# ESP32_Custom.net
KiCad netlist of a schematic drawn in Altium Designer
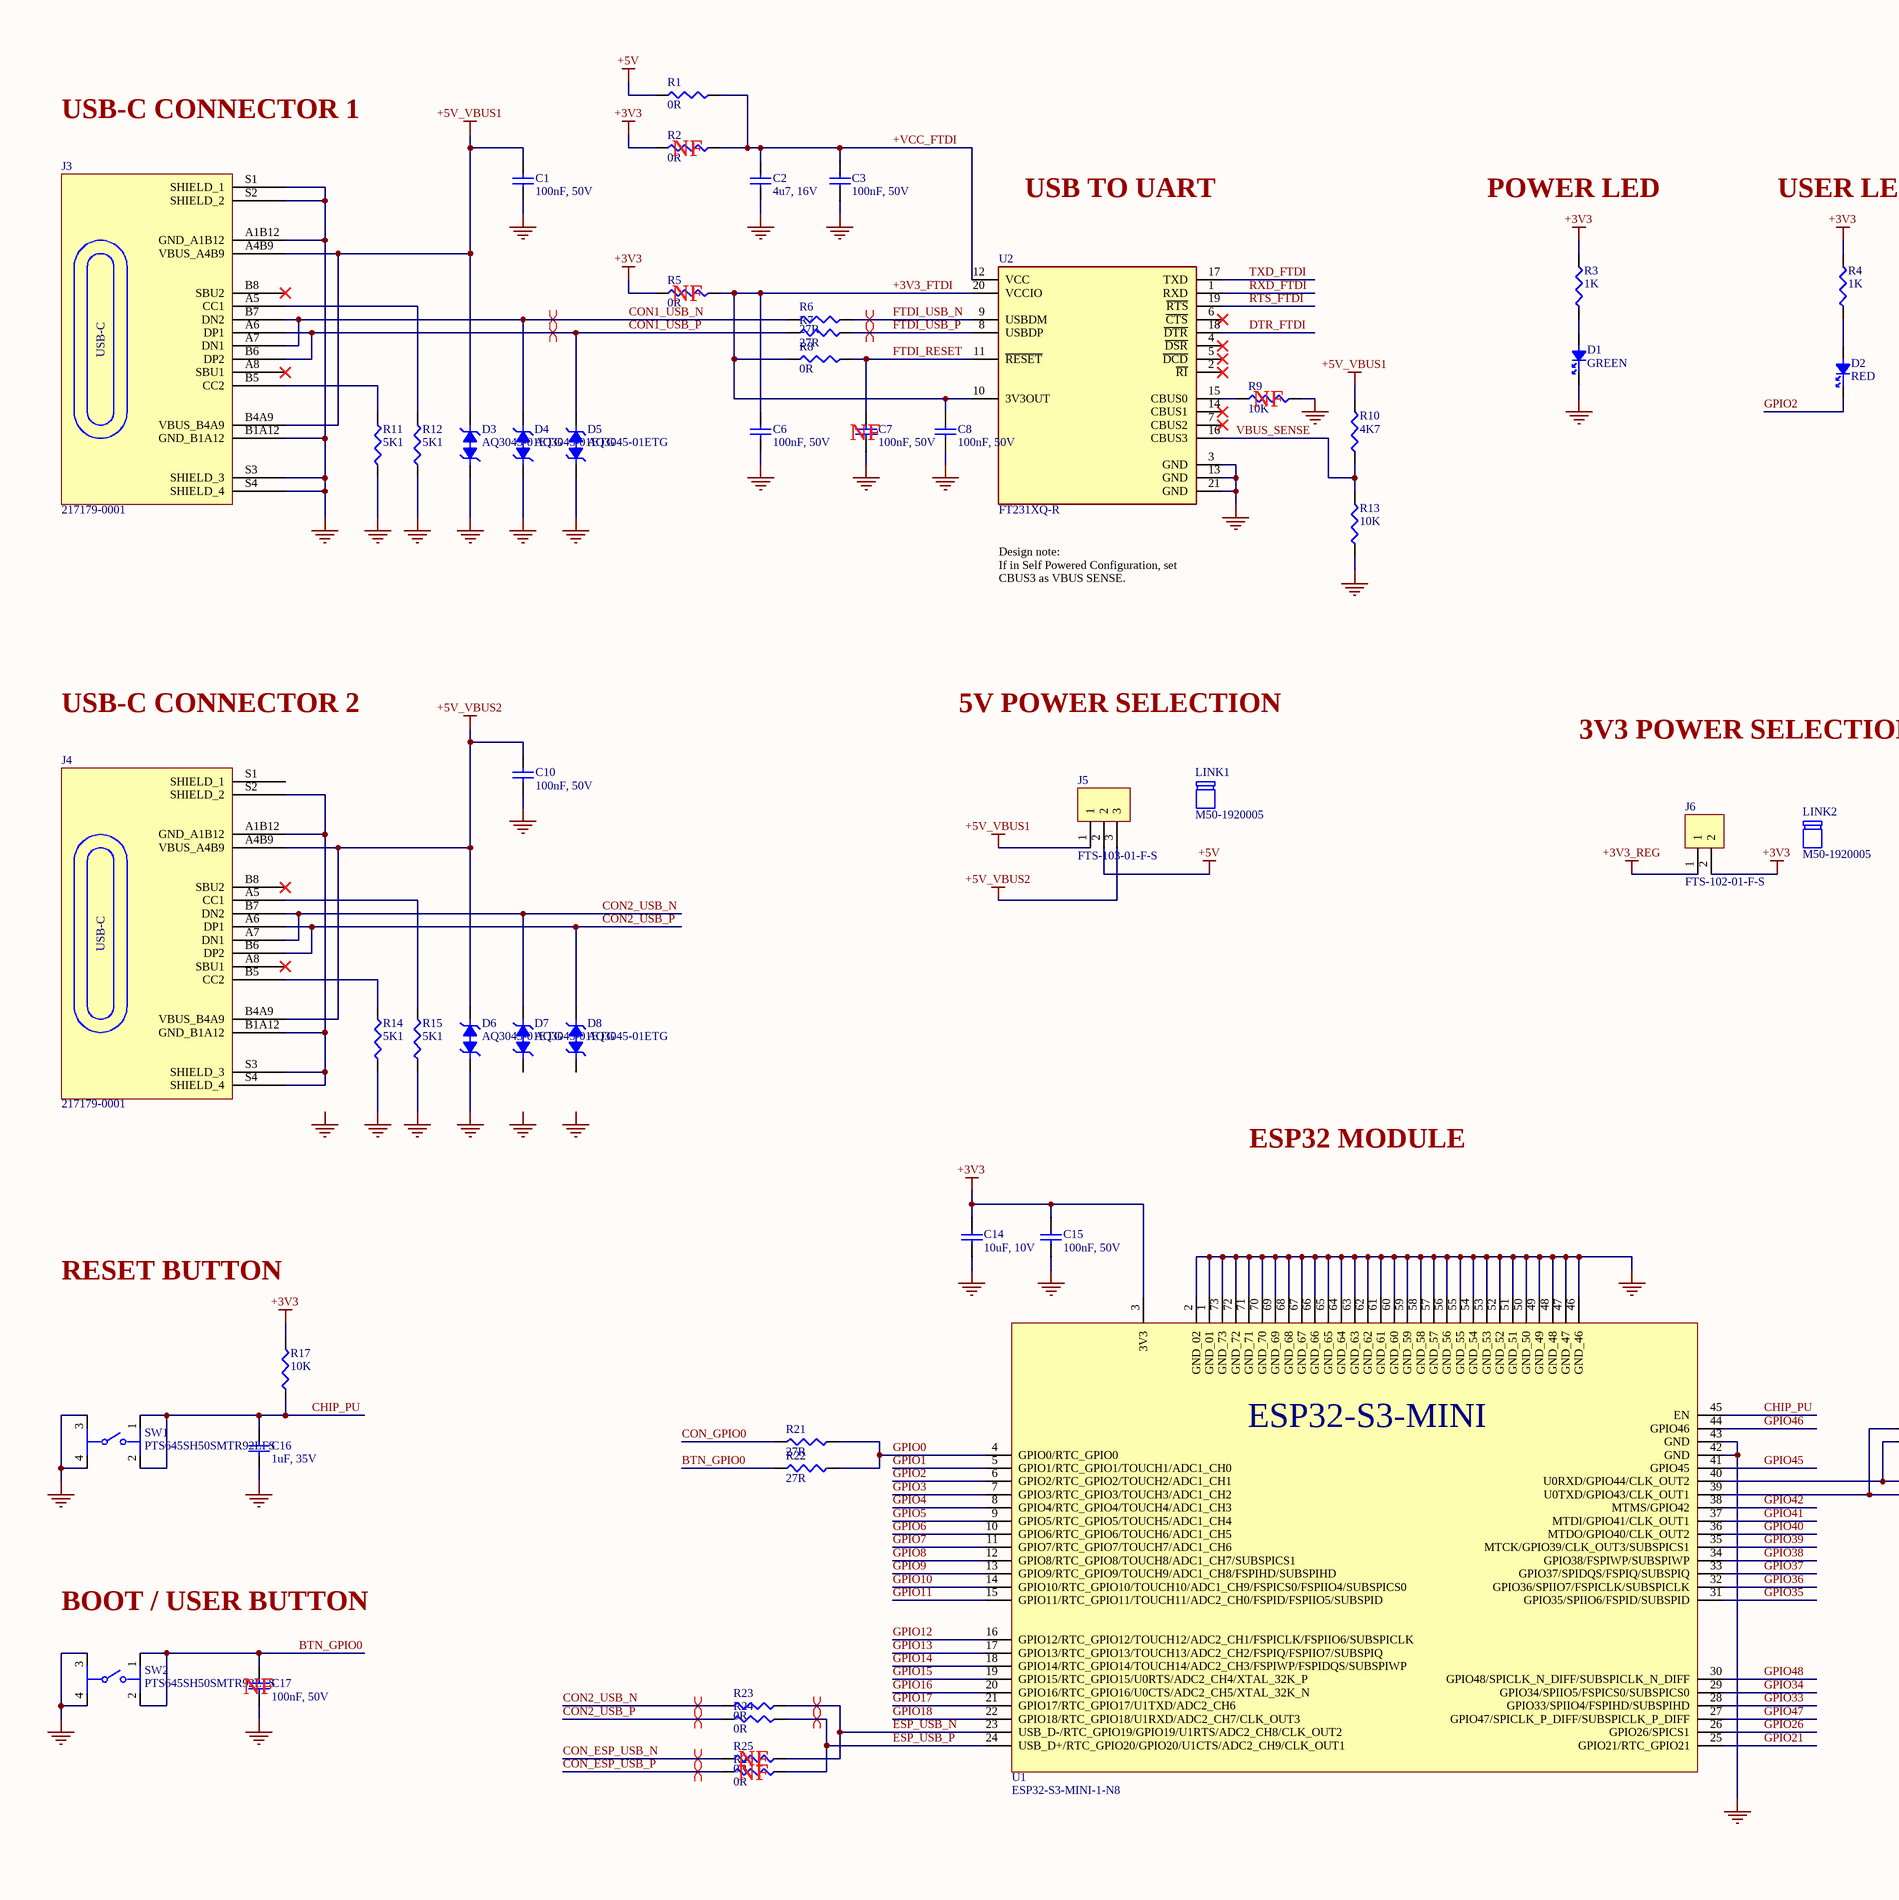
[diagram p0: ESP32 Custom.SchDoc, left]
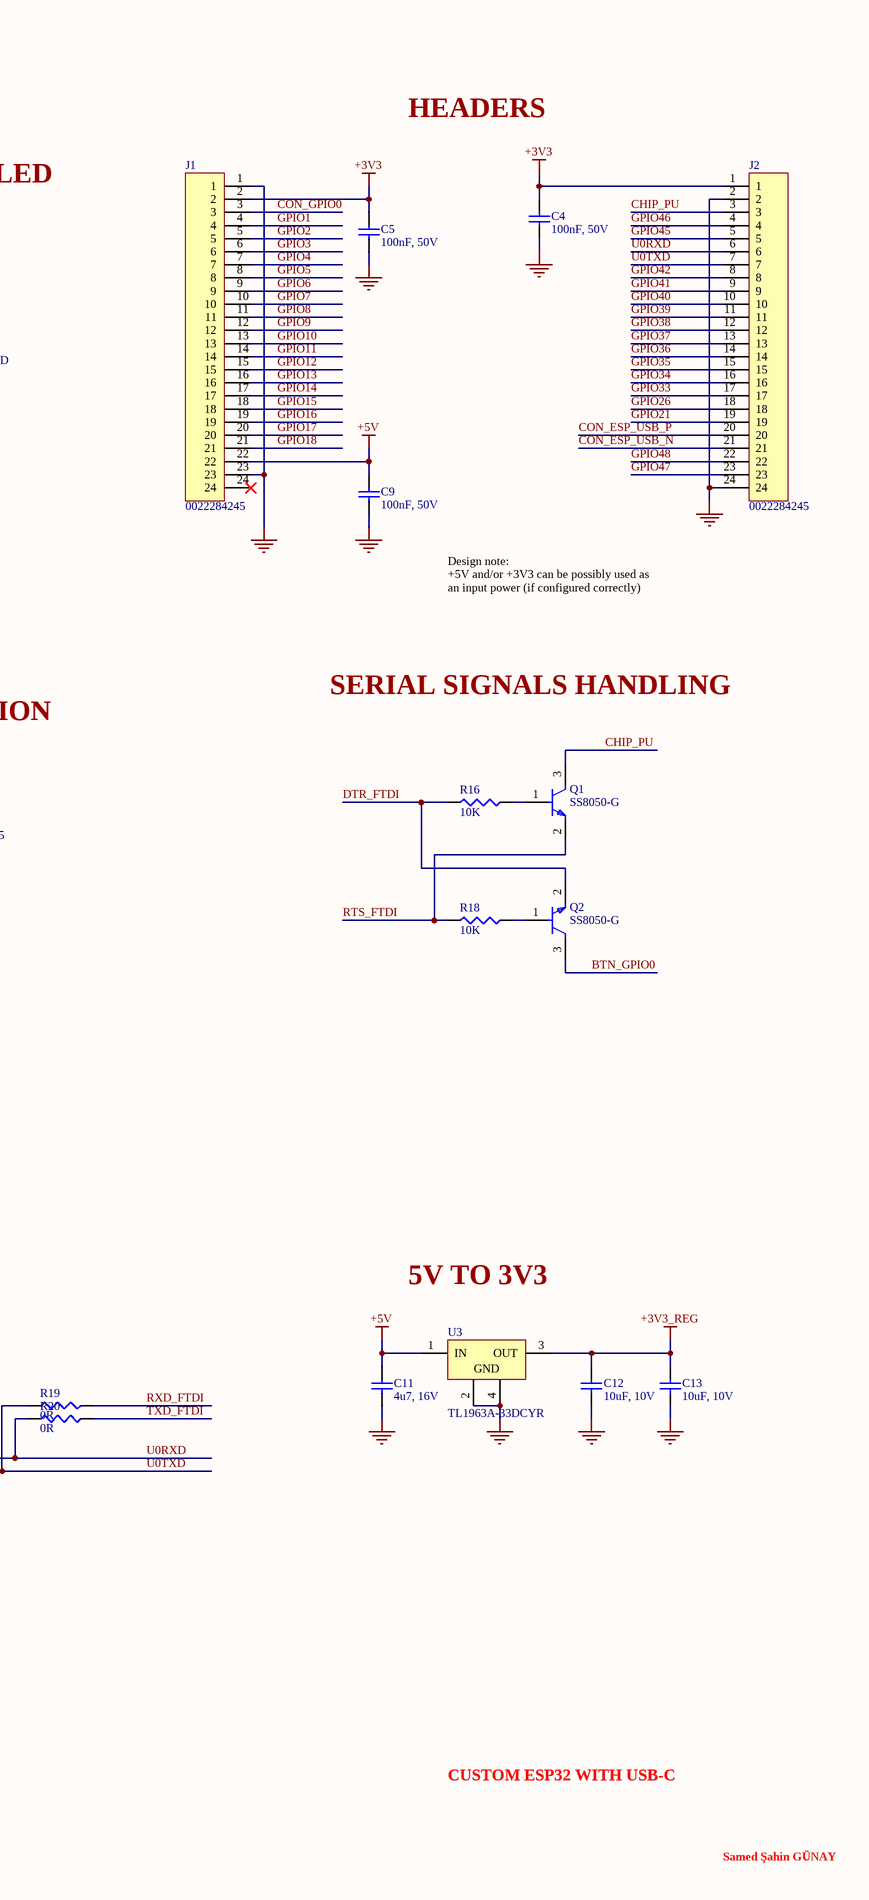
[diagram p1: ESP32 Custom.SchDoc, right]

(export (version "E")
  (design (tool "Eeschema 10.0.6"))
  (components
    (comp (ref "C1")
      (value "100nF, 50V")
      (footprint "CAPC1005X55N")
      (description "CAP CER 0.1UF 50V X7R 0402")
      (fields
        (field (name "MANUFACTURER") "Samsung")
        (field (name "MANUFACTURER PART NUMBER") "CL05B104KB54PNC")
      )
      (libsource (lib "Schlib") (part "CL05B104KB54PNC"))
    )
    (comp (ref "C2")
      (value "4u7, 16V")
      (footprint "CAPC1005X55N")
      (description "CAP CER 4.7UF 16V X5R 0402")
      (fields
        (field (name "MANUFACTURER") "Samsung")
        (field (name "MANUFACTURER PART NUMBER") "CL05A475MO5NUNC")
      )
      (libsource (lib "Schlib") (part "CL05A475MO5NUNC"))
    )
    (comp (ref "C3")
      (value "100nF, 50V")
      (footprint "CAPC1005X55N")
      (description "CAP CER 0.1UF 50V X7R 0402")
      (fields
        (field (name "MANUFACTURER") "Samsung")
        (field (name "MANUFACTURER PART NUMBER") "CL05B104KB54PNC")
      )
      (libsource (lib "Schlib") (part "CL05B104KB54PNC"))
    )
    (comp (ref "C4")
      (value "100nF, 50V")
      (footprint "CAPC1005X55N")
      (description "CAP CER 0.1UF 50V X7R 0402")
      (fields
        (field (name "MANUFACTURER") "Samsung")
        (field (name "MANUFACTURER PART NUMBER") "CL05B104KB54PNC")
      )
      (libsource (lib "Schlib") (part "CL05B104KB54PNC"))
    )
    (comp (ref "C5")
      (value "100nF, 50V")
      (footprint "CAPC1005X55N")
      (description "CAP CER 0.1UF 50V X7R 0402")
      (fields
        (field (name "MANUFACTURER") "Samsung")
        (field (name "MANUFACTURER PART NUMBER") "CL05B104KB54PNC")
      )
      (libsource (lib "Schlib") (part "CL05B104KB54PNC"))
    )
    (comp (ref "C6")
      (value "100nF, 50V")
      (footprint "CAPC1005X55N")
      (description "CAP CER 0.1UF 50V X7R 0402")
      (fields
        (field (name "MANUFACTURER") "Samsung")
        (field (name "MANUFACTURER PART NUMBER") "CL05B104KB54PNC")
      )
      (libsource (lib "Schlib") (part "CL05B104KB54PNC"))
    )
    (comp (ref "C7")
      (value "100nF, 50V")
      (footprint "CAPC1005X55N")
      (description "CAP CER 0.1UF 50V X7R 0402")
      (fields
        (field (name "MANUFACTURER") "Samsung")
        (field (name "MANUFACTURER PART NUMBER") "CL05B104KB54PNC")
      )
      (libsource (lib "Schlib") (part "CL05B104KB54PNC"))
    )
    (comp (ref "C8")
      (value "100nF, 50V")
      (footprint "CAPC1005X55N")
      (description "CAP CER 0.1UF 50V X7R 0402")
      (fields
        (field (name "MANUFACTURER") "Samsung")
        (field (name "MANUFACTURER PART NUMBER") "CL05B104KB54PNC")
      )
      (libsource (lib "Schlib") (part "CL05B104KB54PNC"))
    )
    (comp (ref "C9")
      (value "100nF, 50V")
      (footprint "CAPC1005X55N")
      (description "CAP CER 0.1UF 50V X7R 0402")
      (fields
        (field (name "MANUFACTURER") "Samsung")
        (field (name "MANUFACTURER PART NUMBER") "CL05B104KB54PNC")
      )
      (libsource (lib "Schlib") (part "CL05B104KB54PNC"))
    )
    (comp (ref "C10")
      (value "100nF, 50V")
      (footprint "CAPC1005X55N")
      (description "CAP CER 0.1UF 50V X7R 0402")
      (fields
        (field (name "MANUFACTURER") "Samsung")
        (field (name "MANUFACTURER PART NUMBER") "CL05B104KB54PNC")
      )
      (libsource (lib "Schlib") (part "CL05B104KB54PNC"))
    )
    (comp (ref "C11")
      (value "4u7, 16V")
      (footprint "CAPC1005X55N")
      (description "CAP CER 4.7UF 16V X5R 0402")
      (fields
        (field (name "MANUFACTURER") "Samsung")
        (field (name "MANUFACTURER PART NUMBER") "CL05A475MO5NUNC")
      )
      (libsource (lib "Schlib") (part "CL05A475MO5NUNC"))
    )
    (comp (ref "C12")
      (value "10uF, 10V")
      (footprint "CAPC1005X55N")
      (description "CAP CER 10UF 10V X5R 0402")
      (fields
        (field (name "MANUFACTURER") "Samsung")
        (field (name "MANUFACTURER PART NUMBER") "CL05A106MP8NUB8")
      )
      (libsource (lib "Schlib") (part "CL05A106MP8NUB8"))
    )
    (comp (ref "C13")
      (value "10uF, 10V")
      (footprint "CAPC1005X55N")
      (description "CAP CER 10UF 10V X5R 0402")
      (fields
        (field (name "MANUFACTURER") "Samsung")
        (field (name "MANUFACTURER PART NUMBER") "CL05A106MP8NUB8")
      )
      (libsource (lib "Schlib") (part "CL05A106MP8NUB8"))
    )
    (comp (ref "C14")
      (value "10uF, 10V")
      (footprint "CAPC1005X55N")
      (description "CAP CER 10UF 10V X5R 0402")
      (fields
        (field (name "MANUFACTURER") "Samsung")
        (field (name "MANUFACTURER PART NUMBER") "CL05A106MP8NUB8")
      )
      (libsource (lib "Schlib") (part "CL05A106MP8NUB8"))
    )
    (comp (ref "C15")
      (value "100nF, 50V")
      (footprint "CAPC1005X55N")
      (description "CAP CER 0.1UF 50V X7R 0402")
      (fields
        (field (name "MANUFACTURER") "Samsung")
        (field (name "MANUFACTURER PART NUMBER") "CL05B104KB54PNC")
      )
      (libsource (lib "Schlib") (part "CL05B104KB54PNC"))
    )
    (comp (ref "C16")
      (value "1uF, 35V")
      (footprint "CAPC1005X55N")
      (description "CAP CER 1UF 35V X5R 0402")
      (fields
        (field (name "MANUFACTURER") "Samsung")
        (field (name "MANUFACTURER PART NUMBER") "CL05A105KL5NRNC")
      )
      (libsource (lib "Schlib") (part "CL05A105KL5NRNC"))
    )
    (comp (ref "C17")
      (value "100nF, 50V")
      (footprint "CAPC1005X55N")
      (description "CAP CER 0.1UF 50V X7R 0402")
      (fields
        (field (name "MANUFACTURER") "Samsung")
        (field (name "MANUFACTURER PART NUMBER") "CL05B104KB54PNC")
      )
      (libsource (lib "Schlib") (part "CL05B104KB54PNC"))
    )
    (comp (ref "D1")
      (value "GREEN")
      (footprint "LED0402G")
      (description "LED YLW-GRN 0402 SMD")
      (fields
        (field (name "MANUFACTURER") "Vishay")
        (field (name "MANUFACTURER PART NUMBER") "VLMG1500-GS08")
      )
      (libsource (lib "Schlib") (part "VLMG1500-GS08"))
    )
    (comp (ref "D2")
      (value "RED")
      (footprint "LED0402R")
      (description "LED RED 0402 SMD")
      (fields
        (field (name "MANUFACTURER") "Vishay")
        (field (name "MANUFACTURER PART NUMBER") "VLMS1500-GS08")
      )
      (libsource (lib "Schlib") (part "VLMS1500-GS08"))
    )
    (comp (ref "D3")
      (value "AQ3045-01ETG")
      (footprint "SOD882")
      (description "TVS DIODE 5.3VWM 12VC SOD882")
      (fields (field (name "MANUFACTURER") "Littelfuse") (field (name "LCSC PART NUMBER") "C3710326"))
      (libsource (lib "Schlib") (part "AQ3045-01ETG"))
    )
    (comp (ref "D4")
      (value "AQ3045-01ETG")
      (footprint "SOD882")
      (description "TVS DIODE 5.3VWM 12VC SOD882")
      (fields (field (name "MANUFACTURER") "Littelfuse") (field (name "LCSC PART NUMBER") "C3710326"))
      (libsource (lib "Schlib") (part "AQ3045-01ETG"))
    )
    (comp (ref "D5")
      (value "AQ3045-01ETG")
      (footprint "SOD882")
      (description "TVS DIODE 5.3VWM 12VC SOD882")
      (fields (field (name "MANUFACTURER") "Littelfuse") (field (name "LCSC PART NUMBER") "C3710326"))
      (libsource (lib "Schlib") (part "AQ3045-01ETG"))
    )
    (comp (ref "D6")
      (value "AQ3045-01ETG")
      (footprint "SOD882")
      (description "TVS DIODE 5.3VWM 12VC SOD882")
      (fields (field (name "MANUFACTURER") "Littelfuse") (field (name "LCSC PART NUMBER") "C3710326"))
      (libsource (lib "Schlib") (part "AQ3045-01ETG"))
    )
    (comp (ref "D7")
      (value "AQ3045-01ETG")
      (footprint "SOD882")
      (description "TVS DIODE 5.3VWM 12VC SOD882")
      (fields (field (name "MANUFACTURER") "Littelfuse") (field (name "LCSC PART NUMBER") "C3710326"))
      (libsource (lib "Schlib") (part "AQ3045-01ETG"))
    )
    (comp (ref "D8")
      (value "AQ3045-01ETG")
      (footprint "SOD882")
      (description "TVS DIODE 5.3VWM 12VC SOD882")
      (fields (field (name "MANUFACTURER") "Littelfuse") (field (name "LCSC PART NUMBER") "C3710326"))
      (libsource (lib "Schlib") (part "AQ3045-01ETG"))
    )
    (comp (ref "J1")
      (value "0022284245")
      (footprint "HDR_1X24_2.54MM")
      (description "CONN HEADER VERT 24POS 2.54MM")
      (fields (field (name "MANUFACTURER") "Molex") (field (name "LCSC PART NUMBER") "C7145888"))
      (libsource (lib "") (part "0022284245_1"))
    )
    (comp (ref "J2")
      (value "0022284245")
      (footprint "HDR_1X24_2.54MM")
      (description "CONN HEADER VERT 24POS 2.54MM")
      (fields (field (name "MANUFACTURER") "Molex") (field (name "LCSC PART NUMBER") "C7145888"))
      (libsource (lib "Schlib") (part "0022284245"))
    )
    (comp (ref "J3")
      (value "217179-0001")
      (footprint "FP-2171790001-MFG")
      (description "CONN RCP USB2.0 TYP C 24P SMD RA")
      (fields (field (name "MANUFACTURER") "Molex") (field (name "LCSC PART NUMBER") "C3197684"))
      (libsource (lib "Schlib") (part "217179-0001"))
    )
    (comp (ref "J4")
      (value "217179-0001")
      (footprint "FP-2171790001-MFG")
      (description "CONN RCP USB2.0 TYP C 24P SMD RA")
      (fields (field (name "MANUFACTURER") "Molex") (field (name "LCSC PART NUMBER") "C3197684"))
      (libsource (lib "Schlib") (part "217179-0001"))
    )
    (comp (ref "J5")
      (value "FTS-103-01-F-S")
      (footprint "HDR_1X3_1.27MM")
      (description "CONN HEADER VERT 3POS 1.27MM")
      (fields (field (name "MANUFACTURER") "Samtec") (field (name "LCSC PART NUMBER") "C3333578"))
      (libsource (lib "Schlib") (part "FTS-103-01-F-S"))
    )
    (comp (ref "J6")
      (value "FTS-102-01-F-S")
      (footprint "HDR_1X2_1.27MM")
      (description "CONN HEADER VERT 2POS 1.27MM")
      (fields (field (name "MANUFACTURER") "Samtec") (field (name "LCSC PART NUMBER") "C6045317"))
      (libsource (lib "Schlib") (part "FTS-102-01-F-S"))
    )
    (comp (ref "LINK1")
      (value "M50-1920005")
      (description "CONN SHUNT 1.27MM RED")
      (fields (field (name "MANUFACTURER") "Harwin") (field (name "LCSC PART NUMBER") "C6985646"))
      (libsource (lib "Schlib") (part "M50-1920005"))
    )
    (comp (ref "LINK2")
      (value "M50-1920005")
      (description "CONN SHUNT 1.27MM RED")
      (fields (field (name "MANUFACTURER") "Harwin") (field (name "LCSC PART NUMBER") "C6985646"))
      (libsource (lib "Schlib") (part "M50-1920005"))
    )
    (comp (ref "Q1")
      (value "SS8050-G")
      (footprint "FP-SS8050-G-IPC_B")
      (description "TRANS NPN 25V 1.5A SOT23-3")
      (fields (field (name "MANUFACTURER") "Comchip") (field (name "LCSC PART NUMBER") "C164886"))
      (libsource (lib "Schlib") (part "SS8050-G"))
    )
    (comp (ref "Q2")
      (value "SS8050-G")
      (footprint "FP-SS8050-G-IPC_B")
      (description "TRANS NPN 25V 1.5A SOT23-3")
      (fields (field (name "MANUFACTURER") "Comchip") (field (name "LCSC PART NUMBER") "C164886"))
      (libsource (lib "Schlib") (part "SS8050-G"))
    )
    (comp (ref "R1")
      (value "0R")
      (footprint "RESC1005X37N")
      (description "RES 0 OHM JUMPER 1/16W 0402")
      (fields
        (field (name "MANUFACTURER") "Yageo")
        (field (name "MANUFACTURER PART NUMBER") "RC0402JR-070RL")
      )
      (libsource (lib "Schlib") (part "RC0402JR-070RL"))
    )
    (comp (ref "R2")
      (value "0R")
      (footprint "RESC1005X37N")
      (description "RES 0 OHM JUMPER 1/16W 0402")
      (fields
        (field (name "MANUFACTURER") "Yageo")
        (field (name "MANUFACTURER PART NUMBER") "RC0402JR-070RL")
      )
      (libsource (lib "Schlib") (part "RC0402JR-070RL"))
    )
    (comp (ref "R3")
      (value "1K")
      (footprint "RESC1005X37N")
      (description "RES 1K OHM 1% 1/16W 0402")
      (fields
        (field (name "MANUFACTURER") "Yageo")
        (field (name "MANUFACTURER PART NUMBER") "RC0402FR-071KL")
      )
      (libsource (lib "Schlib") (part "RC0402FR-071KL"))
    )
    (comp (ref "R4")
      (value "1K")
      (footprint "RESC1005X37N")
      (description "RES 1K OHM 1% 1/16W 0402")
      (fields
        (field (name "MANUFACTURER") "Yageo")
        (field (name "MANUFACTURER PART NUMBER") "RC0402FR-071KL")
      )
      (libsource (lib "Schlib") (part "RC0402FR-071KL"))
    )
    (comp (ref "R5")
      (value "0R")
      (footprint "RESC1005X37N")
      (description "RES 0 OHM JUMPER 1/16W 0402")
      (fields
        (field (name "MANUFACTURER") "Yageo")
        (field (name "MANUFACTURER PART NUMBER") "RC0402JR-070RL")
      )
      (libsource (lib "Schlib") (part "RC0402JR-070RL"))
    )
    (comp (ref "R6")
      (value "27R")
      (footprint "RESC1005X37N")
      (description "RES 27 OHM 1% 1/16W 0402")
      (fields
        (field (name "MANUFACTURER") "Yageo")
        (field (name "MANUFACTURER PART NUMBER") "RC0402FR-0727RL")
      )
      (libsource (lib "Schlib") (part "RC0402FR-0727RL"))
    )
    (comp (ref "R7")
      (value "27R")
      (footprint "RESC1005X37N")
      (description "RES 27 OHM 1% 1/16W 0402")
      (fields
        (field (name "MANUFACTURER") "Yageo")
        (field (name "MANUFACTURER PART NUMBER") "RC0402FR-0727RL")
      )
      (libsource (lib "Schlib") (part "RC0402FR-0727RL"))
    )
    (comp (ref "R8")
      (value "0R")
      (footprint "RESC1005X37N")
      (description "RES 0 OHM JUMPER 1/16W 0402")
      (fields
        (field (name "MANUFACTURER") "Yageo")
        (field (name "MANUFACTURER PART NUMBER") "RC0402JR-070RL")
      )
      (libsource (lib "Schlib") (part "RC0402JR-070RL"))
    )
    (comp (ref "R9")
      (value "10K")
      (footprint "RESC1005X37N")
      (description "RES SMD 10K OHM 1% 1/16W 0402")
      (fields
        (field (name "MANUFACTURER") "Yageo")
        (field (name "MANUFACTURER PART NUMBER") "AC0402FR-0710KL")
      )
      (libsource (lib "Schlib") (part "AC0402FR-0710KL"))
    )
    (comp (ref "R10")
      (value "4K7")
      (footprint "RESC1005X37N")
      (description "RES 4.7K OHM 1% 1/16W 0402")
      (fields
        (field (name "MANUFACTURER") "Yageo")
        (field (name "MANUFACTURER PART NUMBER") "RC0402FR-074K7L")
      )
      (libsource (lib "Schlib") (part "RC0402FR-074K7L"))
    )
    (comp (ref "R11")
      (value "5K1")
      (footprint "RESC1005X37N")
      (description "RES SMD 5.1K OHM 1% 1/16W 0402")
      (fields
        (field (name "MANUFACTURER") "Yageo")
        (field (name "MANUFACTURER PART NUMBER") "AC0402FR-075K1L")
      )
      (libsource (lib "Schlib") (part "AC0402FR-075K1L"))
    )
    (comp (ref "R12")
      (value "5K1")
      (footprint "RESC1005X37N")
      (description "RES SMD 5.1K OHM 1% 1/16W 0402")
      (fields
        (field (name "MANUFACTURER") "Yageo")
        (field (name "MANUFACTURER PART NUMBER") "AC0402FR-075K1L")
      )
      (libsource (lib "Schlib") (part "AC0402FR-075K1L"))
    )
    (comp (ref "R13")
      (value "10K")
      (footprint "RESC1005X37N")
      (description "RES SMD 10K OHM 1% 1/16W 0402")
      (fields
        (field (name "MANUFACTURER") "Yageo")
        (field (name "MANUFACTURER PART NUMBER") "AC0402FR-0710KL")
      )
      (libsource (lib "Schlib") (part "AC0402FR-0710KL"))
    )
    (comp (ref "R14")
      (value "5K1")
      (footprint "RESC1005X37N")
      (description "RES SMD 5.1K OHM 1% 1/16W 0402")
      (fields
        (field (name "MANUFACTURER") "Yageo")
        (field (name "MANUFACTURER PART NUMBER") "AC0402FR-075K1L")
      )
      (libsource (lib "Schlib") (part "AC0402FR-075K1L"))
    )
    (comp (ref "R15")
      (value "5K1")
      (footprint "RESC1005X37N")
      (description "RES SMD 5.1K OHM 1% 1/16W 0402")
      (fields
        (field (name "MANUFACTURER") "Yageo")
        (field (name "MANUFACTURER PART NUMBER") "AC0402FR-075K1L")
      )
      (libsource (lib "Schlib") (part "AC0402FR-075K1L"))
    )
    (comp (ref "R16")
      (value "10K")
      (footprint "RESC1005X37N")
      (description "RES SMD 10K OHM 1% 1/16W 0402")
      (fields
        (field (name "MANUFACTURER") "Yageo")
        (field (name "MANUFACTURER PART NUMBER") "AC0402FR-0710KL")
      )
      (libsource (lib "Schlib") (part "AC0402FR-0710KL"))
    )
    (comp (ref "R17")
      (value "10K")
      (footprint "RESC1005X37N")
      (description "RES SMD 10K OHM 1% 1/16W 0402")
      (fields
        (field (name "MANUFACTURER") "Yageo")
        (field (name "MANUFACTURER PART NUMBER") "AC0402FR-0710KL")
      )
      (libsource (lib "Schlib") (part "AC0402FR-0710KL"))
    )
    (comp (ref "R18")
      (value "10K")
      (footprint "RESC1005X37N")
      (description "RES SMD 10K OHM 1% 1/16W 0402")
      (fields
        (field (name "MANUFACTURER") "Yageo")
        (field (name "MANUFACTURER PART NUMBER") "AC0402FR-0710KL")
      )
      (libsource (lib "Schlib") (part "AC0402FR-0710KL"))
    )
    (comp (ref "R19")
      (value "0R")
      (footprint "RESC1005X37N")
      (description "RES 0 OHM JUMPER 1/16W 0402")
      (fields
        (field (name "MANUFACTURER") "Yageo")
        (field (name "MANUFACTURER PART NUMBER") "RC0402JR-070RL")
      )
      (libsource (lib "Schlib") (part "RC0402JR-070RL"))
    )
    (comp (ref "R20")
      (value "0R")
      (footprint "RESC1005X37N")
      (description "RES 0 OHM JUMPER 1/16W 0402")
      (fields
        (field (name "MANUFACTURER") "Yageo")
        (field (name "MANUFACTURER PART NUMBER") "RC0402JR-070RL")
      )
      (libsource (lib "Schlib") (part "RC0402JR-070RL"))
    )
    (comp (ref "R21")
      (value "27R")
      (footprint "RESC1005X37N")
      (description "RES 27 OHM 1% 1/16W 0402")
      (fields
        (field (name "MANUFACTURER") "Yageo")
        (field (name "MANUFACTURER PART NUMBER") "RC0402FR-0727RL")
      )
      (libsource (lib "Schlib") (part "RC0402FR-0727RL"))
    )
    (comp (ref "R22")
      (value "27R")
      (footprint "RESC1005X37N")
      (description "RES 27 OHM 1% 1/16W 0402")
      (fields
        (field (name "MANUFACTURER") "Yageo")
        (field (name "MANUFACTURER PART NUMBER") "RC0402FR-0727RL")
      )
      (libsource (lib "Schlib") (part "RC0402FR-0727RL"))
    )
    (comp (ref "R23")
      (value "0R")
      (footprint "RESC1005X37N")
      (description "RES 0 OHM JUMPER 1/16W 0402")
      (fields
        (field (name "MANUFACTURER") "Yageo")
        (field (name "MANUFACTURER PART NUMBER") "RC0402JR-070RL")
      )
      (libsource (lib "Schlib") (part "RC0402JR-070RL"))
    )
    (comp (ref "R24")
      (value "0R")
      (footprint "RESC1005X37N")
      (description "RES 0 OHM JUMPER 1/16W 0402")
      (fields
        (field (name "MANUFACTURER") "Yageo")
        (field (name "MANUFACTURER PART NUMBER") "RC0402JR-070RL")
      )
      (libsource (lib "Schlib") (part "RC0402JR-070RL"))
    )
    (comp (ref "R25")
      (value "0R")
      (footprint "RESC1005X37N")
      (description "RES 0 OHM JUMPER 1/16W 0402")
      (fields
        (field (name "MANUFACTURER") "Yageo")
        (field (name "MANUFACTURER PART NUMBER") "RC0402JR-070RL")
      )
      (libsource (lib "Schlib") (part "RC0402JR-070RL"))
    )
    (comp (ref "R26")
      (value "0R")
      (footprint "RESC1005X37N")
      (description "RES 0 OHM JUMPER 1/16W 0402")
      (fields
        (field (name "MANUFACTURER") "Yageo")
        (field (name "MANUFACTURER PART NUMBER") "RC0402JR-070RL")
      )
      (libsource (lib "Schlib") (part "RC0402JR-070RL"))
    )
    (comp (ref "SW1")
      (value "PTS645SH50SMTR92LFS")
      (footprint "FP-PTS645SH50SMTR92LFS-MFG")
      (description "SWITCH TACTILE SPST-NO 0.05A 12V")
      (fields (field (name "MANUFACTURER") "ITT C&K") (field (name "LCSC PART NUMBER") "C221869"))
      (libsource (lib "Schlib") (part "PTS645SH50SMTR92LFS"))
    )
    (comp (ref "SW2")
      (value "PTS645SH50SMTR92LFS")
      (footprint "FP-PTS645SH50SMTR92LFS-MFG")
      (description "SWITCH TACTILE SPST-NO 0.05A 12V")
      (fields (field (name "MANUFACTURER") "ITT C&K") (field (name "LCSC PART NUMBER") "C221869"))
      (libsource (lib "Schlib") (part "PTS645SH50SMTR92LFS"))
    )
    (comp (ref "U1")
      (value "ESP32-S3-MINI-1-N8")
      (footprint "XCVR_ESP32-S3-MINI-1-N8")
      (description "SMD Module, ESP32-S3FN8, 8 mb Sp")
      (fields (field (name "MANUFACTURER") "Espressif Systems") (field (name "LCSC PART NUMBER") "C2913206"))
      (libsource (lib "Schlib") (part "ESP32-S3-MINI-1-N8"))
    )
    (comp (ref "U2")
      (value "FT231XQ-R")
      (footprint "FP-QFN-20-IPC_B")
      (description "IC USB SERIAL FULL UART 20QFN")
      (fields (field (name "MANUFACTURER") "FTDI") (field (name "LCSC PART NUMBER") "C132159"))
      (libsource (lib "Schlib") (part "FT231XQ-R"))
    )
    (comp (ref "U3")
      (value "TL1963A-33DCYR")
      (footprint "DCY0004A_N")
      (description "IC REG LINEAR 3.3V 1.5A SOT223-4")
      (fields (field (name "MANUFACTURER") "Texas Instruments") (field (name "LCSC PART NUMBER") "C181262"))
      (libsource (lib "Schlib") (part "TL1963A-33DCYR"))
    )
  )
  (nets
    (net (code "1") (name "+3V3") (class "Default")
      (node (ref "C14") (pin "2") (pinfunction "2_2") (pintype "passive"))
      (node (ref "C15") (pin "2") (pinfunction "2_2") (pintype "passive"))
      (node (ref "C4") (pin "2") (pinfunction "2_2") (pintype "passive"))
      (node (ref "C5") (pin "2") (pinfunction "2_2") (pintype "passive"))
      (node (ref "J1") (pin "2") (pinfunction "2_2") (pintype "passive"))
      (node (ref "J2") (pin "1") (pinfunction "1_1") (pintype "passive"))
      (node (ref "J6") (pin "2") (pinfunction "2_2") (pintype "passive"))
      (node (ref "R17") (pin "2") (pinfunction "2_2") (pintype "passive"))
      (node (ref "R2") (pin "1") (pinfunction "1_1") (pintype "passive"))
      (node (ref "R3") (pin "2") (pinfunction "2_2") (pintype "passive"))
      (node (ref "R4") (pin "2") (pinfunction "2_2") (pintype "passive"))
      (node (ref "R5") (pin "1") (pinfunction "1_1") (pintype "passive"))
      (node (ref "U1") (pin "3") (pinfunction "3V3_3") (pintype "passive"))
    )
    (net (code "2") (name "+3V3_REG") (class "Default")
      (node (ref "C12") (pin "2") (pinfunction "2_2") (pintype "passive"))
      (node (ref "C13") (pin "2") (pinfunction "2_2") (pintype "passive"))
      (node (ref "J6") (pin "1") (pinfunction "1_1") (pintype "passive"))
      (node (ref "U3") (pin "3") (pinfunction "OUT_3") (pintype "power_in"))
    )
    (net (code "3") (name "+5V") (class "Default")
      (node (ref "C11") (pin "2") (pinfunction "2_2") (pintype "passive"))
      (node (ref "C9") (pin "2") (pinfunction "2_2") (pintype "passive"))
      (node (ref "J1") (pin "22") (pinfunction "22_22") (pintype "passive"))
      (node (ref "J5") (pin "2") (pinfunction "2_2") (pintype "passive"))
      (node (ref "R1") (pin "1") (pinfunction "1_1") (pintype "passive"))
      (node (ref "U3") (pin "1") (pinfunction "IN_1") (pintype "power_in"))
    )
    (net (code "4") (name "+5V_VBUS1") (class "Default")
      (node (ref "C1") (pin "2") (pinfunction "2_2") (pintype "passive"))
      (node (ref "D3") (pin "2") (pinfunction "2_2") (pintype "passive"))
      (node (ref "J3") (pin "A4B9") (pinfunction "VBUS_A4B9_A4B9") (pintype "passive"))
      (node (ref "J3") (pin "B4A9") (pinfunction "VBUS_B4A9_B4A9") (pintype "passive"))
      (node (ref "J5") (pin "1") (pinfunction "1_1") (pintype "passive"))
      (node (ref "R10") (pin "2") (pinfunction "2_2") (pintype "passive"))
    )
    (net (code "5") (name "+5V_VBUS2") (class "Default")
      (node (ref "C10") (pin "2") (pinfunction "2_2") (pintype "passive"))
      (node (ref "D6") (pin "2") (pinfunction "2_2") (pintype "passive"))
      (node (ref "J4") (pin "A4B9") (pinfunction "VBUS_A4B9_A4B9") (pintype "passive"))
      (node (ref "J4") (pin "B4A9") (pinfunction "VBUS_B4A9_B4A9") (pintype "passive"))
      (node (ref "J5") (pin "3") (pinfunction "3_3") (pintype "passive"))
    )
    (net (code "6") (name "/+3V3_FTDI") (class "Default")
      (node (ref "C6") (pin "2") (pinfunction "2_2") (pintype "passive"))
      (node (ref "C8") (pin "2") (pinfunction "2_2") (pintype "passive"))
      (node (ref "R5") (pin "2") (pinfunction "2_2") (pintype "passive"))
      (node (ref "R8") (pin "1") (pinfunction "1_1") (pintype "passive"))
      (node (ref "U2") (pin "10") (pinfunction "3V3OUT_10") (pintype "passive"))
      (node (ref "U2") (pin "20") (pinfunction "VCCIO_20") (pintype "passive"))
    )
    (net (code "7") (name "/+VCC_FTDI") (class "Default")
      (node (ref "C2") (pin "2") (pinfunction "2_2") (pintype "passive"))
      (node (ref "C3") (pin "2") (pinfunction "2_2") (pintype "passive"))
      (node (ref "R1") (pin "2") (pinfunction "2_2") (pintype "passive"))
      (node (ref "R2") (pin "2") (pinfunction "2_2") (pintype "passive"))
      (node (ref "U2") (pin "12") (pinfunction "VCC_12") (pintype "passive"))
    )
    (net (code "8") (name "/BTN_GPIO0") (class "Default")
      (node (ref "C17") (pin "2") (pinfunction "2_2") (pintype "passive"))
      (node (ref "Q2") (pin "3") (pinfunction "C_3") (pintype "passive"))
      (node (ref "R22") (pin "1") (pinfunction "1_1") (pintype "passive"))
      (node (ref "SW2") (pin "1") (pinfunction "1_1") (pintype "passive"))
      (node (ref "SW2") (pin "2") (pinfunction "2_2") (pintype "passive"))
    )
    (net (code "9") (name "/CHIP_PU") (class "Default")
      (node (ref "C16") (pin "2") (pinfunction "2_2") (pintype "passive"))
      (node (ref "J2") (pin "3") (pinfunction "3_3") (pintype "passive"))
      (node (ref "Q1") (pin "3") (pinfunction "C_3") (pintype "passive"))
      (node (ref "R17") (pin "1") (pinfunction "1_1") (pintype "passive"))
      (node (ref "SW1") (pin "1") (pinfunction "1_1") (pintype "passive"))
      (node (ref "SW1") (pin "2") (pinfunction "2_2") (pintype "passive"))
      (node (ref "U1") (pin "45") (pinfunction "EN_45") (pintype "passive"))
    )
    (net (code "10") (name "/CON1_USB_N") (class "Default")
      (node (ref "D4") (pin "2") (pinfunction "2_2") (pintype "passive"))
      (node (ref "J3") (pin "A7") (pinfunction "DN1_A7") (pintype "passive"))
      (node (ref "J3") (pin "B7") (pinfunction "DN2_B7") (pintype "passive"))
      (node (ref "R6") (pin "1") (pinfunction "1_1") (pintype "passive"))
    )
    (net (code "11") (name "/CON1_USB_P") (class "Default")
      (node (ref "D5") (pin "2") (pinfunction "2_2") (pintype "passive"))
      (node (ref "J3") (pin "A6") (pinfunction "DP1_A6") (pintype "passive"))
      (node (ref "J3") (pin "B6") (pinfunction "DP2_B6") (pintype "passive"))
      (node (ref "R7") (pin "1") (pinfunction "1_1") (pintype "passive"))
    )
    (net (code "12") (name "/CON2_USB_N") (class "Default")
      (node (ref "D7") (pin "2") (pinfunction "2_2") (pintype "passive"))
      (node (ref "J4") (pin "A7") (pinfunction "DN1_A7") (pintype "passive"))
      (node (ref "J4") (pin "B7") (pinfunction "DN2_B7") (pintype "passive"))
      (node (ref "R23") (pin "1") (pinfunction "1_1") (pintype "passive"))
    )
    (net (code "13") (name "/CON2_USB_P") (class "Default")
      (node (ref "D8") (pin "2") (pinfunction "2_2") (pintype "passive"))
      (node (ref "J4") (pin "A6") (pinfunction "DP1_A6") (pintype "passive"))
      (node (ref "J4") (pin "B6") (pinfunction "DP2_B6") (pintype "passive"))
      (node (ref "R24") (pin "1") (pinfunction "1_1") (pintype "passive"))
    )
    (net (code "14") (name "/CON_ESP_USB_N") (class "Default")
      (node (ref "J2") (pin "21") (pinfunction "21_21") (pintype "passive"))
      (node (ref "R25") (pin "1") (pinfunction "1_1") (pintype "passive"))
    )
    (net (code "15") (name "/CON_ESP_USB_P") (class "Default")
      (node (ref "J2") (pin "20") (pinfunction "20_20") (pintype "passive"))
      (node (ref "R26") (pin "1") (pinfunction "1_1") (pintype "passive"))
    )
    (net (code "16") (name "/CON_GPIO0") (class "Default")
      (node (ref "J1") (pin "3") (pinfunction "3_3") (pintype "passive"))
      (node (ref "R21") (pin "1") (pinfunction "1_1") (pintype "passive"))
    )
    (net (code "17") (name "/DTR_FTDI") (class "Default")
      (node (ref "Q2") (pin "2") (pinfunction "E_2") (pintype "passive"))
      (node (ref "R16") (pin "1") (pinfunction "1_1") (pintype "passive"))
      (node (ref "U2") (pin "18") (pinfunction "~{DTR}_18") (pintype "passive"))
    )
    (net (code "18") (name "/ESP_USB_N") (class "Default")
      (node (ref "R23") (pin "2") (pinfunction "2_2") (pintype "passive"))
      (node (ref "R25") (pin "2") (pinfunction "2_2") (pintype "passive"))
      (node (ref "U1") (pin "23") (pinfunction "USB_D-/RTC_GPIO19/GPIO19/U1RTS/ADC2_CH8/CLK_OUT2_23") (pintype "passive"))
    )
    (net (code "19") (name "/ESP_USB_P") (class "Default")
      (node (ref "R24") (pin "2") (pinfunction "2_2") (pintype "passive"))
      (node (ref "R26") (pin "2") (pinfunction "2_2") (pintype "passive"))
      (node (ref "U1") (pin "24") (pinfunction "USB_D+/RTC_GPIO20/GPIO20/U1CTS/ADC2_CH9/CLK_OUT1_24") (pintype "passive"))
    )
    (net (code "20") (name "/FTDI_RESET") (class "Default")
      (node (ref "C7") (pin "2") (pinfunction "2_2") (pintype "passive"))
      (node (ref "R8") (pin "2") (pinfunction "2_2") (pintype "passive"))
      (node (ref "U2") (pin "11") (pinfunction "~{RESET}_11") (pintype "passive"))
    )
    (net (code "21") (name "/FTDI_USB_N") (class "Default")
      (node (ref "R6") (pin "2") (pinfunction "2_2") (pintype "passive"))
      (node (ref "U2") (pin "9") (pinfunction "USBDM_9") (pintype "passive"))
    )
    (net (code "22") (name "/FTDI_USB_P") (class "Default")
      (node (ref "R7") (pin "2") (pinfunction "2_2") (pintype "passive"))
      (node (ref "U2") (pin "8") (pinfunction "USBDP_8") (pintype "passive"))
    )
    (net (code "23") (name "/GPIO0") (class "Default")
      (node (ref "R21") (pin "2") (pinfunction "2_2") (pintype "passive"))
      (node (ref "R22") (pin "2") (pinfunction "2_2") (pintype "passive"))
      (node (ref "U1") (pin "4") (pinfunction "GPIO0/RTC_GPIO0_4") (pintype "passive"))
    )
    (net (code "24") (name "/GPIO1") (class "Default")
      (node (ref "J1") (pin "4") (pinfunction "4_4") (pintype "passive"))
      (node (ref "U1") (pin "5") (pinfunction "GPIO1/RTC_GPIO1/TOUCH1/ADC1_CH0_5") (pintype "passive"))
    )
    (net (code "25") (name "/GPIO2") (class "Default")
      (node (ref "D2") (pin "1") (pinfunction "1_1") (pintype "passive"))
      (node (ref "J1") (pin "5") (pinfunction "5_5") (pintype "passive"))
      (node (ref "U1") (pin "6") (pinfunction "GPIO2/RTC_GPIO2/TOUCH2/ADC1_CH1_6") (pintype "passive"))
    )
    (net (code "26") (name "/GPIO3") (class "Default")
      (node (ref "J1") (pin "6") (pinfunction "6_6") (pintype "passive"))
      (node (ref "U1") (pin "7") (pinfunction "GPIO3/RTC_GPIO3/TOUCH3/ADC1_CH2_7") (pintype "passive"))
    )
    (net (code "27") (name "/GPIO4") (class "Default")
      (node (ref "J1") (pin "7") (pinfunction "7_7") (pintype "passive"))
      (node (ref "U1") (pin "8") (pinfunction "GPIO4/RTC_GPIO4/TOUCH4/ADC1_CH3_8") (pintype "passive"))
    )
    (net (code "28") (name "/GPIO5") (class "Default")
      (node (ref "J1") (pin "8") (pinfunction "8_8") (pintype "passive"))
      (node (ref "U1") (pin "9") (pinfunction "GPIO5/RTC_GPIO5/TOUCH5/ADC1_CH4_9") (pintype "passive"))
    )
    (net (code "29") (name "/GPIO6") (class "Default")
      (node (ref "J1") (pin "9") (pinfunction "9_9") (pintype "passive"))
      (node (ref "U1") (pin "10") (pinfunction "GPIO6/RTC_GPIO6/TOUCH6/ADC1_CH5_10") (pintype "passive"))
    )
    (net (code "30") (name "/GPIO7") (class "Default")
      (node (ref "J1") (pin "10") (pinfunction "10_10") (pintype "passive"))
      (node (ref "U1") (pin "11") (pinfunction "GPIO7/RTC_GPIO7/TOUCH7/ADC1_CH6_11") (pintype "passive"))
    )
    (net (code "31") (name "/GPIO8") (class "Default")
      (node (ref "J1") (pin "11") (pinfunction "11_11") (pintype "passive"))
      (node (ref "U1") (pin "12") (pinfunction "GPIO8/RTC_GPIO8/TOUCH8/ADC1_CH7/SUBSPICS1_12") (pintype "passive"))
    )
    (net (code "32") (name "/GPIO9") (class "Default")
      (node (ref "J1") (pin "12") (pinfunction "12_12") (pintype "passive"))
      (node (ref "U1") (pin "13") (pinfunction "GPIO9/RTC_GPIO9/TOUCH9/ADC1_CH8/FSPIHD/SUBSPIHD_13") (pintype "passive"))
    )
    (net (code "33") (name "/GPIO10") (class "Default")
      (node (ref "J1") (pin "13") (pinfunction "13_13") (pintype "passive"))
      (node (ref "U1") (pin "14") (pinfunction "GPIO10/RTC_GPIO10/TOUCH10/ADC1_CH9/FSPICS0/FSPIIO4/SUBSPICS0_14") (pintype "passive"))
    )
    (net (code "34") (name "/GPIO11") (class "Default")
      (node (ref "J1") (pin "14") (pinfunction "14_14") (pintype "passive"))
      (node (ref "U1") (pin "15") (pinfunction "GPIO11/RTC_GPIO11/TOUCH11/ADC2_CH0/FSPID/FSPIIO5/SUBSPID_15") (pintype "passive"))
    )
    (net (code "35") (name "/GPIO12") (class "Default")
      (node (ref "J1") (pin "15") (pinfunction "15_15") (pintype "passive"))
      (node (ref "U1") (pin "16") (pinfunction "GPIO12/RTC_GPIO12/TOUCH12/ADC2_CH1/FSPICLK/FSPIIO6/SUBSPICLK_16") (pintype "passive"))
    )
    (net (code "36") (name "/GPIO13") (class "Default")
      (node (ref "J1") (pin "16") (pinfunction "16_16") (pintype "passive"))
      (node (ref "U1") (pin "17") (pinfunction "GPIO13/RTC_GPIO13/TOUCH13/ADC2_CH2/FSPIQ/FSPIIO7/SUBSPIQ_17") (pintype "passive"))
    )
    (net (code "37") (name "/GPIO14") (class "Default")
      (node (ref "J1") (pin "17") (pinfunction "17_17") (pintype "passive"))
      (node (ref "U1") (pin "18") (pinfunction "GPIO14/RTC_GPIO14/TOUCH14/ADC2_CH3/FSPIWP/FSPIDQS/SUBSPIWP_18") (pintype "passive"))
    )
    (net (code "38") (name "/GPIO15") (class "Default")
      (node (ref "J1") (pin "18") (pinfunction "18_18") (pintype "passive"))
      (node (ref "U1") (pin "19") (pinfunction "GPIO15/RTC_GPIO15/U0RTS/ADC2_CH4/XTAL_32K_P_19") (pintype "passive"))
    )
    (net (code "39") (name "/GPIO16") (class "Default")
      (node (ref "J1") (pin "19") (pinfunction "19_19") (pintype "passive"))
      (node (ref "U1") (pin "20") (pinfunction "GPIO16/RTC_GPIO16/U0CTS/ADC2_CH5/XTAL_32K_N_20") (pintype "passive"))
    )
    (net (code "40") (name "/GPIO17") (class "Default")
      (node (ref "J1") (pin "20") (pinfunction "20_20") (pintype "passive"))
      (node (ref "U1") (pin "21") (pinfunction "GPIO17/RTC_GPIO17/U1TXD/ADC2_CH6_21") (pintype "passive"))
    )
    (net (code "41") (name "/GPIO18") (class "Default")
      (node (ref "J1") (pin "21") (pinfunction "21_21") (pintype "passive"))
      (node (ref "U1") (pin "22") (pinfunction "GPIO18/RTC_GPIO18/U1RXD/ADC2_CH7/CLK_OUT3_22") (pintype "passive"))
    )
    (net (code "42") (name "/GPIO21") (class "Default")
      (node (ref "J2") (pin "19") (pinfunction "19_19") (pintype "passive"))
      (node (ref "U1") (pin "25") (pinfunction "GPIO21/RTC_GPIO21_25") (pintype "passive"))
    )
    (net (code "43") (name "/GPIO26") (class "Default")
      (node (ref "J2") (pin "18") (pinfunction "18_18") (pintype "passive"))
      (node (ref "U1") (pin "26") (pinfunction "GPIO26/SPICS1_26") (pintype "passive"))
    )
    (net (code "44") (name "/GPIO33") (class "Default")
      (node (ref "J2") (pin "17") (pinfunction "17_17") (pintype "passive"))
      (node (ref "U1") (pin "28") (pinfunction "GPIO33/SPIIO4/FSPIHD/SUBSPIHD_28") (pintype "passive"))
    )
    (net (code "45") (name "/GPIO34") (class "Default")
      (node (ref "J2") (pin "16") (pinfunction "16_16") (pintype "passive"))
      (node (ref "U1") (pin "29") (pinfunction "GPIO34/SPIIO5/FSPICS0/SUBSPICS0_29") (pintype "passive"))
    )
    (net (code "46") (name "/GPIO35") (class "Default")
      (node (ref "J2") (pin "15") (pinfunction "15_15") (pintype "passive"))
      (node (ref "U1") (pin "31") (pinfunction "GPIO35/SPIIO6/FSPID/SUBSPID_31") (pintype "passive"))
    )
    (net (code "47") (name "/GPIO36") (class "Default")
      (node (ref "J2") (pin "14") (pinfunction "14_14") (pintype "passive"))
      (node (ref "U1") (pin "32") (pinfunction "GPIO36/SPIIO7/FSPICLK/SUBSPICLK_32") (pintype "passive"))
    )
    (net (code "48") (name "/GPIO37") (class "Default")
      (node (ref "J2") (pin "13") (pinfunction "13_13") (pintype "passive"))
      (node (ref "U1") (pin "33") (pinfunction "GPIO37/SPIDQS/FSPIQ/SUBSPIQ_33") (pintype "passive"))
    )
    (net (code "49") (name "/GPIO38") (class "Default")
      (node (ref "J2") (pin "12") (pinfunction "12_12") (pintype "passive"))
      (node (ref "U1") (pin "34") (pinfunction "GPIO38/FSPIWP/SUBSPIWP_34") (pintype "passive"))
    )
    (net (code "50") (name "/GPIO39") (class "Default")
      (node (ref "J2") (pin "11") (pinfunction "11_11") (pintype "passive"))
      (node (ref "U1") (pin "35") (pinfunction "MTCK/GPIO39/CLK_OUT3/SUBSPICS1_35") (pintype "passive"))
    )
    (net (code "51") (name "/GPIO40") (class "Default")
      (node (ref "J2") (pin "10") (pinfunction "10_10") (pintype "passive"))
      (node (ref "U1") (pin "36") (pinfunction "MTDO/GPIO40/CLK_OUT2_36") (pintype "passive"))
    )
    (net (code "52") (name "/GPIO41") (class "Default")
      (node (ref "J2") (pin "9") (pinfunction "9_9") (pintype "passive"))
      (node (ref "U1") (pin "37") (pinfunction "MTDI/GPIO41/CLK_OUT1_37") (pintype "passive"))
    )
    (net (code "53") (name "/GPIO42") (class "Default")
      (node (ref "J2") (pin "8") (pinfunction "8_8") (pintype "passive"))
      (node (ref "U1") (pin "38") (pinfunction "MTMS/GPIO42_38") (pintype "passive"))
    )
    (net (code "54") (name "/GPIO45") (class "Default")
      (node (ref "J2") (pin "5") (pinfunction "5_5") (pintype "passive"))
      (node (ref "U1") (pin "41") (pinfunction "GPIO45_41") (pintype "passive"))
    )
    (net (code "55") (name "/GPIO46") (class "Default")
      (node (ref "J2") (pin "4") (pinfunction "4_4") (pintype "passive"))
      (node (ref "U1") (pin "44") (pinfunction "GPIO46_44") (pintype "passive"))
    )
    (net (code "56") (name "/GPIO47") (class "Default")
      (node (ref "J2") (pin "23") (pinfunction "23_23") (pintype "passive"))
      (node (ref "U1") (pin "27") (pinfunction "GPIO47/SPICLK_P_DIFF/SUBSPICLK_P_DIFF_27") (pintype "passive"))
    )
    (net (code "57") (name "/GPIO48") (class "Default")
      (node (ref "J2") (pin "22") (pinfunction "22_22") (pintype "passive"))
      (node (ref "U1") (pin "30") (pinfunction "GPIO48/SPICLK_N_DIFF/SUBSPICLK_N_DIFF_30") (pintype "passive"))
    )
    (net (code "58") (name "/RTS_FTDI") (class "Default")
      (node (ref "Q1") (pin "2") (pinfunction "E_2") (pintype "passive"))
      (node (ref "R18") (pin "1") (pinfunction "1_1") (pintype "passive"))
      (node (ref "U2") (pin "19") (pinfunction "~{RTS}_19") (pintype "passive"))
    )
    (net (code "59") (name "/RXD_FTDI") (class "Default")
      (node (ref "R19") (pin "2") (pinfunction "2_2") (pintype "passive"))
      (node (ref "U2") (pin "1") (pinfunction "RXD_1") (pintype "passive"))
    )
    (net (code "60") (name "/TXD_FTDI") (class "Default")
      (node (ref "R20") (pin "2") (pinfunction "2_2") (pintype "passive"))
      (node (ref "U2") (pin "17") (pinfunction "TXD_17") (pintype "passive"))
    )
    (net (code "61") (name "/U0RXD") (class "Default")
      (node (ref "J2") (pin "6") (pinfunction "6_6") (pintype "passive"))
      (node (ref "R20") (pin "1") (pinfunction "1_1") (pintype "passive"))
      (node (ref "U1") (pin "40") (pinfunction "U0RXD/GPIO44/CLK_OUT2_40") (pintype "passive"))
    )
    (net (code "62") (name "/U0TXD") (class "Default")
      (node (ref "J2") (pin "7") (pinfunction "7_7") (pintype "passive"))
      (node (ref "R19") (pin "1") (pinfunction "1_1") (pintype "passive"))
      (node (ref "U1") (pin "39") (pinfunction "U0TXD/GPIO43/CLK_OUT1_39") (pintype "passive"))
    )
    (net (code "63") (name "/VBUS_SENSE") (class "Default")
      (node (ref "R10") (pin "1") (pinfunction "1_1") (pintype "passive"))
      (node (ref "R13") (pin "1") (pinfunction "1_1") (pintype "passive"))
      (node (ref "U2") (pin "16") (pinfunction "CBUS3_16") (pintype "passive"))
    )
    (net (code "64") (name "GND") (class "Default")
      (node (ref "C1") (pin "1") (pinfunction "1_1") (pintype "passive"))
      (node (ref "C10") (pin "1") (pinfunction "1_1") (pintype "passive"))
      (node (ref "C11") (pin "1") (pinfunction "1_1") (pintype "passive"))
      (node (ref "C12") (pin "1") (pinfunction "1_1") (pintype "passive"))
      (node (ref "C13") (pin "1") (pinfunction "1_1") (pintype "passive"))
      (node (ref "C14") (pin "1") (pinfunction "1_1") (pintype "passive"))
      (node (ref "C15") (pin "1") (pinfunction "1_1") (pintype "passive"))
      (node (ref "C16") (pin "1") (pinfunction "1_1") (pintype "passive"))
      (node (ref "C17") (pin "1") (pinfunction "1_1") (pintype "passive"))
      (node (ref "C2") (pin "1") (pinfunction "1_1") (pintype "passive"))
      (node (ref "C3") (pin "1") (pinfunction "1_1") (pintype "passive"))
      (node (ref "C4") (pin "1") (pinfunction "1_1") (pintype "passive"))
      (node (ref "C5") (pin "1") (pinfunction "1_1") (pintype "passive"))
      (node (ref "C6") (pin "1") (pinfunction "1_1") (pintype "passive"))
      (node (ref "C7") (pin "1") (pinfunction "1_1") (pintype "passive"))
      (node (ref "C8") (pin "1") (pinfunction "1_1") (pintype "passive"))
      (node (ref "C9") (pin "1") (pinfunction "1_1") (pintype "passive"))
      (node (ref "D1") (pin "1") (pinfunction "1_1") (pintype "passive"))
      (node (ref "D3") (pin "1") (pinfunction "1_1") (pintype "passive"))
      (node (ref "D4") (pin "1") (pinfunction "1_1") (pintype "passive"))
      (node (ref "D5") (pin "1") (pinfunction "1_1") (pintype "passive"))
      (node (ref "D6") (pin "1") (pinfunction "1_1") (pintype "passive"))
      (node (ref "J1") (pin "1") (pinfunction "1_1") (pintype "passive"))
      (node (ref "J1") (pin "23") (pinfunction "23_23") (pintype "passive"))
      (node (ref "J2") (pin "2") (pinfunction "2_2") (pintype "passive"))
      (node (ref "J2") (pin "24") (pinfunction "24_24") (pintype "passive"))
      (node (ref "J3") (pin "A1B12") (pinfunction "GND_A1B12_A1B12") (pintype "passive"))
      (node (ref "J3") (pin "B1A12") (pinfunction "GND_B1A12_B1A12") (pintype "passive"))
      (node (ref "J3") (pin "S1") (pinfunction "SHIELD_1_S1") (pintype "passive"))
      (node (ref "J3") (pin "S2") (pinfunction "SHIELD_2_S2") (pintype "passive"))
      (node (ref "J3") (pin "S3") (pinfunction "SHIELD_3_S3") (pintype "passive"))
      (node (ref "J3") (pin "S4") (pinfunction "SHIELD_4_S4") (pintype "passive"))
      (node (ref "R11") (pin "1") (pinfunction "1_1") (pintype "passive"))
      (node (ref "R12") (pin "1") (pinfunction "1_1") (pintype "passive"))
      (node (ref "R13") (pin "2") (pinfunction "2_2") (pintype "passive"))
      (node (ref "R14") (pin "1") (pinfunction "1_1") (pintype "passive"))
      (node (ref "R15") (pin "1") (pinfunction "1_1") (pintype "passive"))
      (node (ref "R9") (pin "2") (pinfunction "2_2") (pintype "passive"))
      (node (ref "SW1") (pin "3") (pinfunction "3_3") (pintype "passive"))
      (node (ref "SW1") (pin "4") (pinfunction "4_4") (pintype "passive"))
      (node (ref "SW2") (pin "3") (pinfunction "3_3") (pintype "passive"))
      (node (ref "SW2") (pin "4") (pinfunction "4_4") (pintype "passive"))
      (node (ref "U1") (pin "1") (pinfunction "GND_01_1") (pintype "passive"))
      (node (ref "U1") (pin "2") (pinfunction "GND_02_2") (pintype "passive"))
      (node (ref "U1") (pin "42") (pinfunction "GND_42") (pintype "passive"))
      (node (ref "U1") (pin "43") (pinfunction "GND_43") (pintype "passive"))
      (node (ref "U1") (pin "46") (pinfunction "GND_46_46") (pintype "passive"))
      (node (ref "U1") (pin "47") (pinfunction "GND_47_47") (pintype "passive"))
      (node (ref "U1") (pin "48") (pinfunction "GND_48_48") (pintype "passive"))
      (node (ref "U1") (pin "49") (pinfunction "GND_49_49") (pintype "passive"))
      (node (ref "U1") (pin "50") (pinfunction "GND_50_50") (pintype "passive"))
      (node (ref "U1") (pin "51") (pinfunction "GND_51_51") (pintype "passive"))
      (node (ref "U1") (pin "52") (pinfunction "GND_52_52") (pintype "passive"))
      (node (ref "U1") (pin "53") (pinfunction "GND_53_53") (pintype "passive"))
      (node (ref "U1") (pin "54") (pinfunction "GND_54_54") (pintype "passive"))
      (node (ref "U1") (pin "55") (pinfunction "GND_55_55") (pintype "passive"))
      (node (ref "U1") (pin "56") (pinfunction "GND_56_56") (pintype "passive"))
      (node (ref "U1") (pin "57") (pinfunction "GND_57_57") (pintype "passive"))
      (node (ref "U1") (pin "58") (pinfunction "GND_58_58") (pintype "passive"))
      (node (ref "U1") (pin "59") (pinfunction "GND_59_59") (pintype "passive"))
      (node (ref "U1") (pin "60") (pinfunction "GND_60_60") (pintype "passive"))
      (node (ref "U1") (pin "61") (pinfunction "GND_61_61") (pintype "passive"))
      (node (ref "U1") (pin "62") (pinfunction "GND_62_62") (pintype "passive"))
      (node (ref "U1") (pin "63") (pinfunction "GND_63_63") (pintype "passive"))
      (node (ref "U1") (pin "64") (pinfunction "GND_64_64") (pintype "passive"))
      (node (ref "U1") (pin "65") (pinfunction "GND_65_65") (pintype "passive"))
      (node (ref "U1") (pin "66") (pinfunction "GND_66_66") (pintype "passive"))
      (node (ref "U1") (pin "67") (pinfunction "GND_67_67") (pintype "passive"))
      (node (ref "U1") (pin "68") (pinfunction "GND_68_68") (pintype "passive"))
      (node (ref "U1") (pin "69") (pinfunction "GND_69_69") (pintype "passive"))
      (node (ref "U1") (pin "70") (pinfunction "GND_70_70") (pintype "passive"))
      (node (ref "U1") (pin "71") (pinfunction "GND_71_71") (pintype "passive"))
      (node (ref "U1") (pin "72") (pinfunction "GND_72_72") (pintype "passive"))
      (node (ref "U1") (pin "73") (pinfunction "GND_73_73") (pintype "passive"))
      (node (ref "U2") (pin "13") (pinfunction "GND_13") (pintype "passive"))
      (node (ref "U2") (pin "21") (pinfunction "GND_21") (pintype "passive"))
      (node (ref "U2") (pin "3") (pinfunction "GND_3") (pintype "passive"))
      (node (ref "U3") (pin "2") (pinfunction "GND_2") (pintype "power_in"))
      (node (ref "U3") (pin "4") (pinfunction "GND_4") (pintype "power_in"))
    )
    (net (code "65") (name "Net-(D1-Pad2)") (class "Default")
      (node (ref "D1") (pin "2") (pinfunction "2_2") (pintype "passive"))
      (node (ref "R3") (pin "1") (pinfunction "1_1") (pintype "passive"))
    )
    (net (code "66") (name "Net-(D2-Pad2)") (class "Default")
      (node (ref "D2") (pin "2") (pinfunction "2_2") (pintype "passive"))
      (node (ref "R4") (pin "1") (pinfunction "1_1") (pintype "passive"))
    )
    (net (code "67") (name "Net-(J3-CC1)") (class "Default")
      (node (ref "J3") (pin "A5") (pinfunction "CC1_A5") (pintype "passive"))
      (node (ref "R12") (pin "2") (pinfunction "2_2") (pintype "passive"))
    )
    (net (code "68") (name "Net-(J3-CC2)") (class "Default")
      (node (ref "J3") (pin "B5") (pinfunction "CC2_B5") (pintype "passive"))
      (node (ref "R11") (pin "2") (pinfunction "2_2") (pintype "passive"))
    )
    (net (code "69") (name "Net-(J4-CC1)") (class "Default")
      (node (ref "J4") (pin "A5") (pinfunction "CC1_A5") (pintype "passive"))
      (node (ref "R15") (pin "2") (pinfunction "2_2") (pintype "passive"))
    )
    (net (code "70") (name "Net-(J4-CC2)") (class "Default")
      (node (ref "J4") (pin "B5") (pinfunction "CC2_B5") (pintype "passive"))
      (node (ref "R14") (pin "2") (pinfunction "2_2") (pintype "passive"))
    )
    (net (code "71") (name "Net-(J4-GND_A1B12)") (class "Default")
      (node (ref "J4") (pin "A1B12") (pinfunction "GND_A1B12_A1B12") (pintype "passive"))
      (node (ref "J4") (pin "B1A12") (pinfunction "GND_B1A12_B1A12") (pintype "passive"))
      (node (ref "J4") (pin "S2") (pinfunction "SHIELD_2_S2") (pintype "passive"))
      (node (ref "J4") (pin "S3") (pinfunction "SHIELD_3_S3") (pintype "passive"))
      (node (ref "J4") (pin "S4") (pinfunction "SHIELD_4_S4") (pintype "passive"))
    )
    (net (code "72") (name "Net-(Q1-B)") (class "Default")
      (node (ref "Q1") (pin "1") (pinfunction "B_1") (pintype "passive"))
      (node (ref "R16") (pin "2") (pinfunction "2_2") (pintype "passive"))
    )
    (net (code "73") (name "Net-(Q2-B)") (class "Default")
      (node (ref "Q2") (pin "1") (pinfunction "B_1") (pintype "passive"))
      (node (ref "R18") (pin "2") (pinfunction "2_2") (pintype "passive"))
    )
    (net (code "74") (name "Net-(U2-CBUS0)") (class "Default")
      (node (ref "R9") (pin "1") (pinfunction "1_1") (pintype "passive"))
      (node (ref "U2") (pin "15") (pinfunction "CBUS0_15") (pintype "passive"))
    )
    (net (code "75") (name "unconnected-(D7-Pad1)") (class "Default")
      (node (ref "D7") (pin "1") (pinfunction "1_1") (pintype "passive"))
    )
    (net (code "76") (name "unconnected-(D8-Pad1)") (class "Default")
      (node (ref "D8") (pin "1") (pinfunction "1_1") (pintype "passive"))
    )
    (net (code "77") (name "unconnected-(J1-Pad24)") (class "Default")
      (node (ref "J1") (pin "24") (pinfunction "24_24") (pintype "passive+no_connect"))
    )
    (net (code "78") (name "unconnected-(J3-SBU1-PadA8)") (class "Default")
      (node (ref "J3") (pin "A8") (pinfunction "SBU1_A8") (pintype "passive+no_connect"))
    )
    (net (code "79") (name "unconnected-(J3-SBU2-PadB8)") (class "Default")
      (node (ref "J3") (pin "B8") (pinfunction "SBU2_B8") (pintype "passive+no_connect"))
    )
    (net (code "80") (name "unconnected-(J4-SBU1-PadA8)") (class "Default")
      (node (ref "J4") (pin "A8") (pinfunction "SBU1_A8") (pintype "passive+no_connect"))
    )
    (net (code "81") (name "unconnected-(J4-SBU2-PadB8)") (class "Default")
      (node (ref "J4") (pin "B8") (pinfunction "SBU2_B8") (pintype "passive+no_connect"))
    )
    (net (code "82") (name "unconnected-(J4-SHIELD_1-PadS1)") (class "Default")
      (node (ref "J4") (pin "S1") (pinfunction "SHIELD_1_S1") (pintype "passive"))
    )
    (net (code "83") (name "unconnected-(U2-CBUS1-Pad14)") (class "Default")
      (node (ref "U2") (pin "14") (pinfunction "CBUS1_14") (pintype "passive+no_connect"))
    )
    (net (code "84") (name "unconnected-(U2-CBUS2-Pad7)") (class "Default")
      (node (ref "U2") (pin "7") (pinfunction "CBUS2_7") (pintype "passive+no_connect"))
    )
    (net (code "85") (name "unconnected-(U2-~{CTS}-Pad6)") (class "Default")
      (node (ref "U2") (pin "6") (pinfunction "~{CTS}_6") (pintype "passive+no_connect"))
    )
    (net (code "86") (name "unconnected-(U2-~{DCD}-Pad5)") (class "Default")
      (node (ref "U2") (pin "5") (pinfunction "~{DCD}_5") (pintype "passive+no_connect"))
    )
    (net (code "87") (name "unconnected-(U2-~{DSR}-Pad4)") (class "Default")
      (node (ref "U2") (pin "4") (pinfunction "~{DSR}_4") (pintype "passive+no_connect"))
    )
    (net (code "88") (name "unconnected-(U2-~{RI}-Pad2)") (class "Default")
      (node (ref "U2") (pin "2") (pinfunction "~{RI}_2") (pintype "passive+no_connect"))
    )
  )
)
